# Lab9.net
KiCad netlist of a schematic drawn in EAGLE
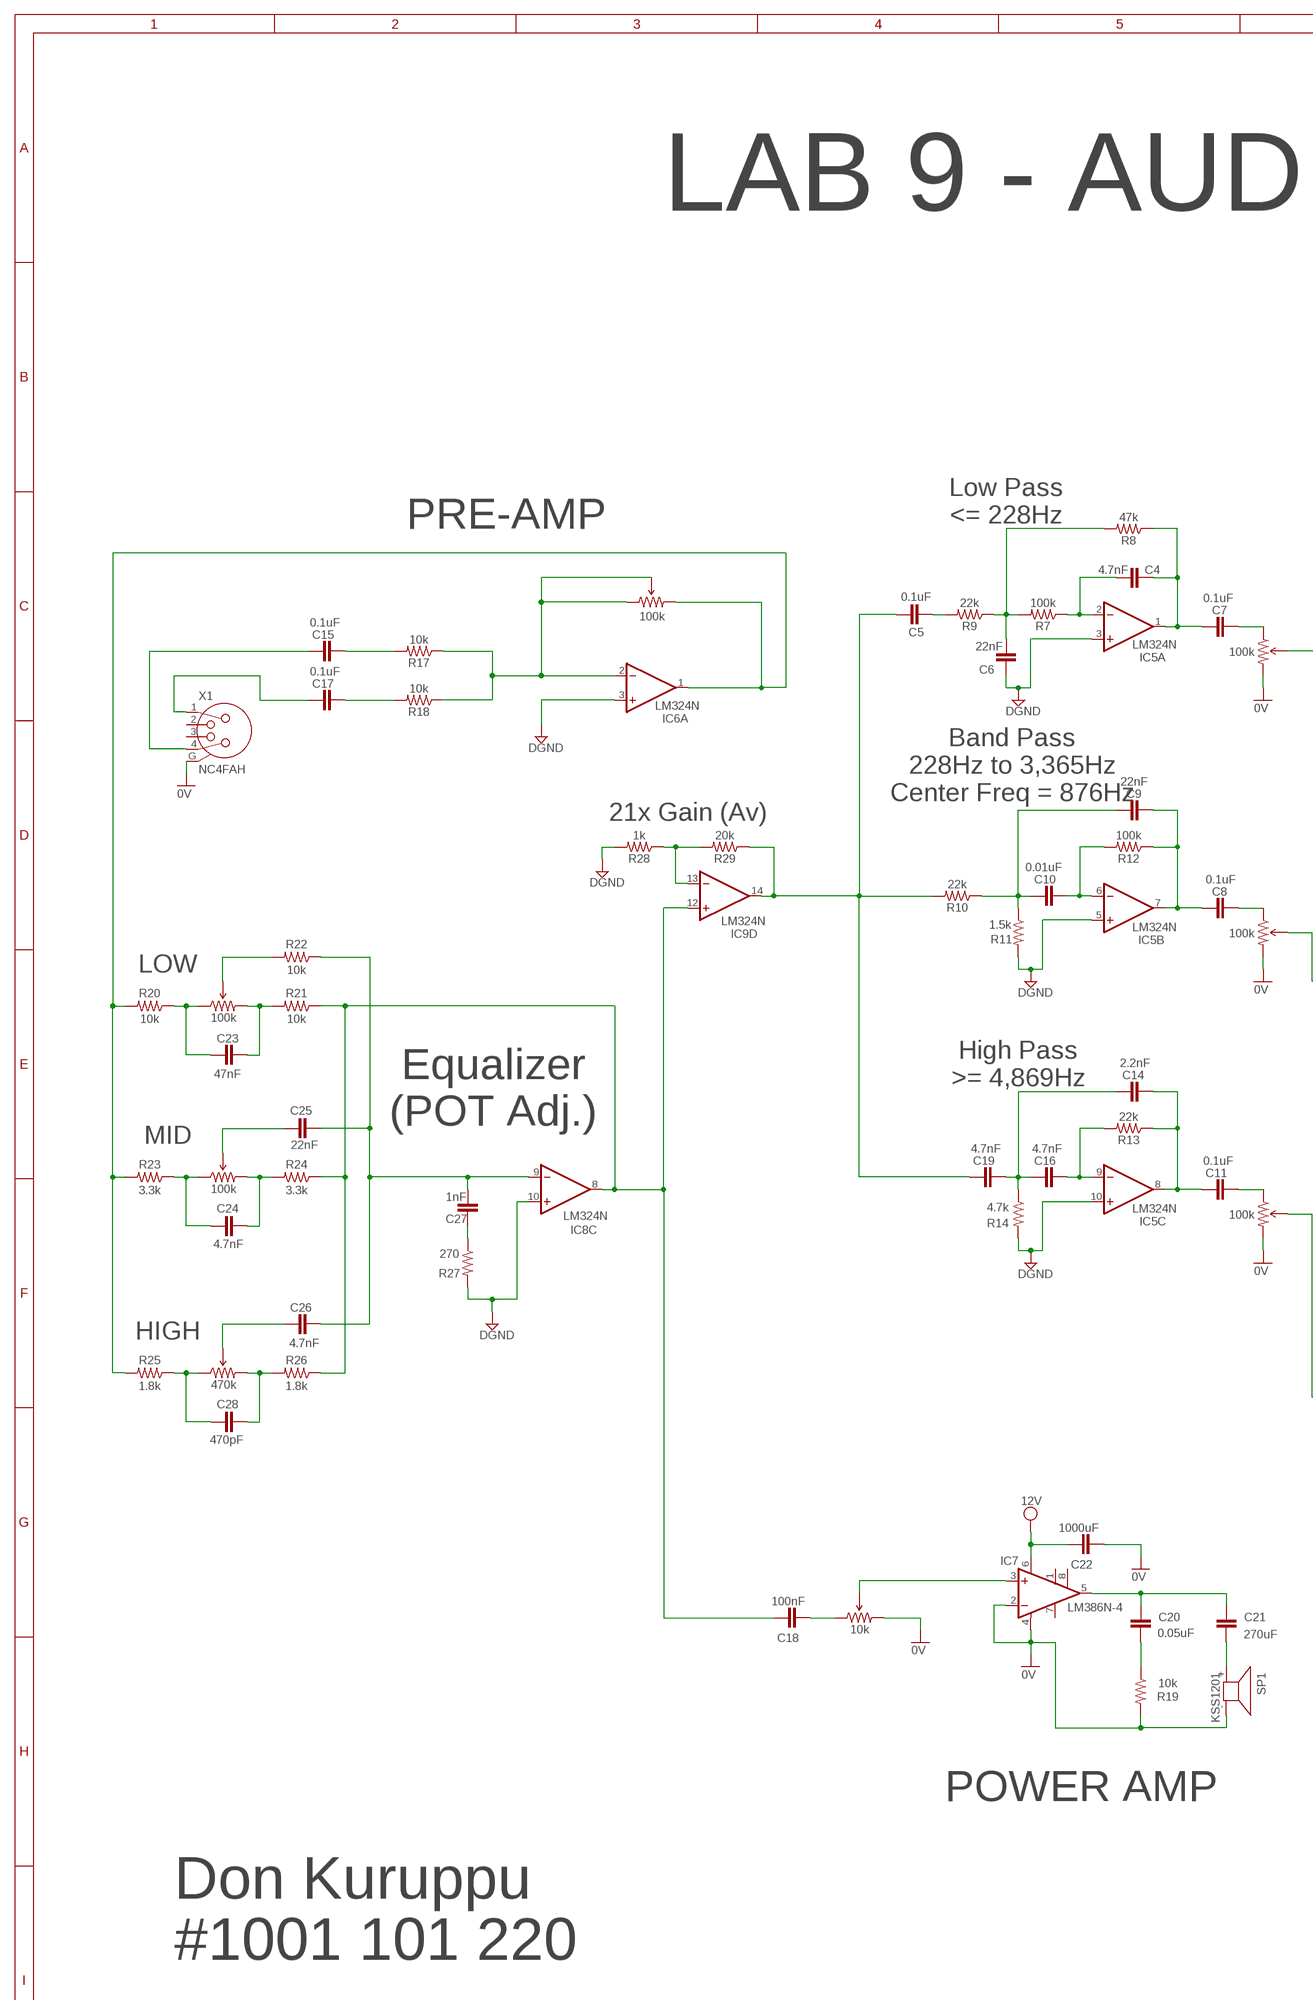
[diagram p0: schematic, sheet 1, part 1 of 2]
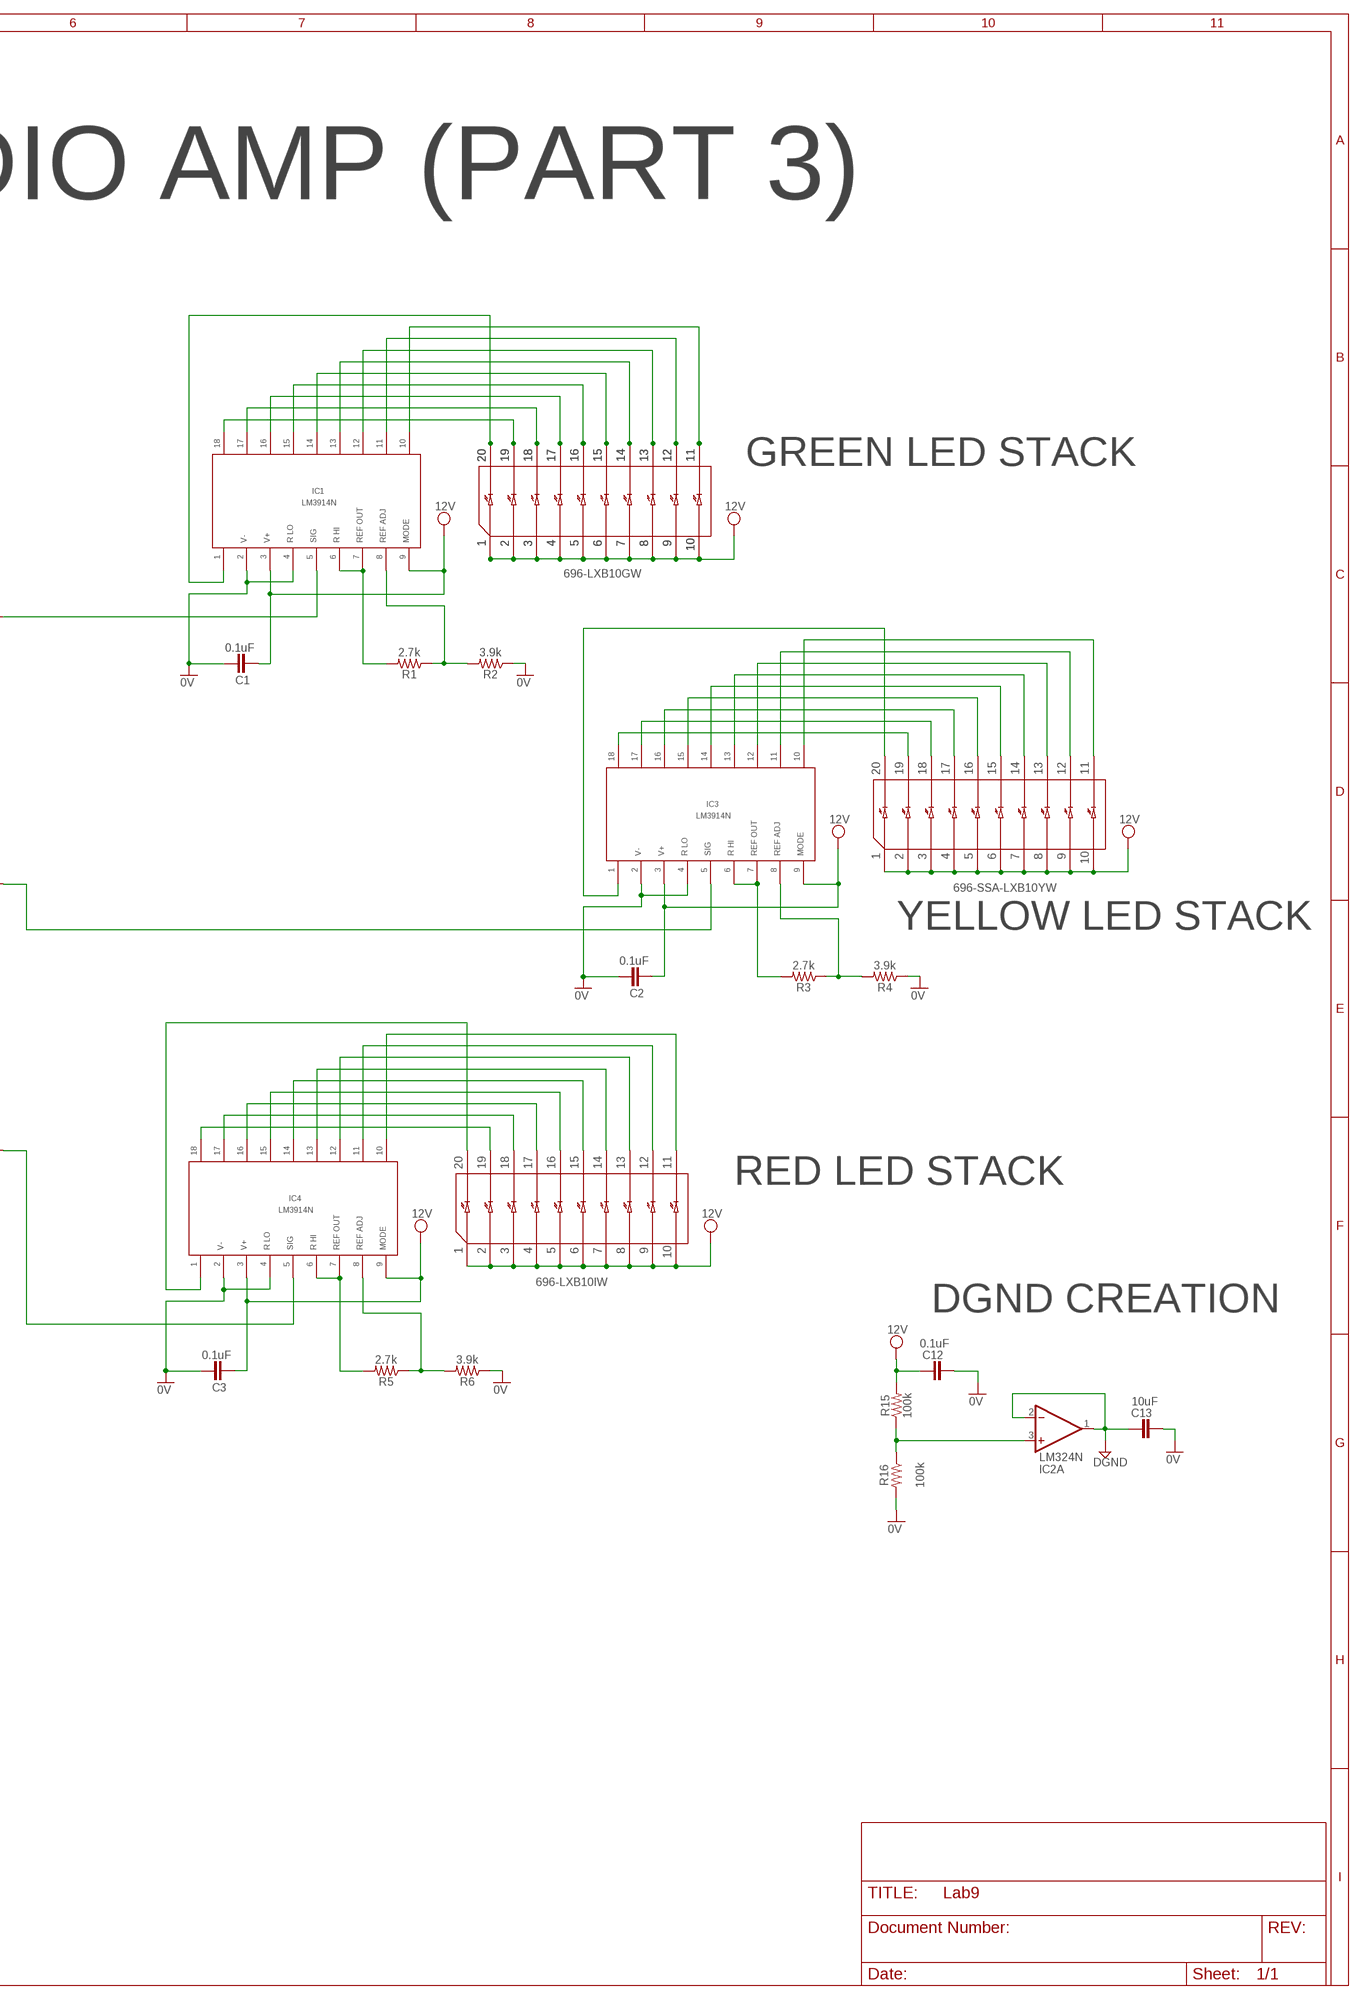
[diagram p1: schematic, sheet 1, part 2 of 2]

(export (version "E")
  (design (tool "Eeschema 10.0.6"))
  (components
    (comp (ref "C1")
      (value "0.1uF")
      (footprint "eagle-import:CAP-PTH-SMALL-KIT")
      (libsource (lib "eagle-import") (part "0.1UF-KIT-EZ-50V-20%"))
    )
    (comp (ref "C2")
      (value "0.1uF")
      (footprint "eagle-import:CAP-PTH-SMALL-KIT")
      (libsource (lib "eagle-import") (part "0.1UF-KIT-EZ-50V-20%"))
    )
    (comp (ref "C3")
      (value "0.1uF")
      (footprint "eagle-import:CAP-PTH-SMALL-KIT")
      (libsource (lib "eagle-import") (part "0.1UF-KIT-EZ-50V-20%"))
    )
    (comp (ref "C4")
      (value "4.7nF")
      (footprint "eagle-import:CAP-PTH-SMALL-KIT")
      (libsource (lib "eagle-import") (part "0.1UF-KIT-EZ-50V-20%"))
    )
    (comp (ref "C5")
      (value "0.1uF")
      (footprint "eagle-import:CAP-PTH-SMALL-KIT")
      (libsource (lib "eagle-import") (part "0.1UF-KIT-EZ-50V-20%"))
    )
    (comp (ref "C6")
      (value "22nF")
      (footprint "eagle-import:CAP-PTH-SMALL-KIT")
      (libsource (lib "eagle-import") (part "0.1UF-KIT-EZ-50V-20%"))
    )
    (comp (ref "C7")
      (value "0.1uF")
      (footprint "eagle-import:CAP-PTH-SMALL-KIT")
      (libsource (lib "eagle-import") (part "0.1UF-KIT-EZ-50V-20%"))
    )
    (comp (ref "C8")
      (value "0.1uF")
      (footprint "eagle-import:CAP-PTH-SMALL-KIT")
      (libsource (lib "eagle-import") (part "0.1UF-KIT-EZ-50V-20%"))
    )
    (comp (ref "C9")
      (value "22nF")
      (footprint "eagle-import:CAP-PTH-SMALL-KIT")
      (libsource (lib "eagle-import") (part "0.1UF-KIT-EZ-50V-20%"))
    )
    (comp (ref "C10")
      (value "0.01uF")
      (footprint "eagle-import:CAP-PTH-SMALL-KIT")
      (libsource (lib "eagle-import") (part "0.1UF-KIT-EZ-50V-20%"))
    )
    (comp (ref "C11")
      (value "0.1uF")
      (footprint "eagle-import:CAP-PTH-SMALL-KIT")
      (libsource (lib "eagle-import") (part "0.1UF-KIT-EZ-50V-20%"))
    )
    (comp (ref "C12")
      (value "0.1uF")
      (footprint "eagle-import:CAP-PTH-SMALL-KIT")
      (libsource (lib "eagle-import") (part "0.1UF-KIT-EZ-50V-20%"))
    )
    (comp (ref "C13")
      (value "10uF")
      (footprint "eagle-import:CAP-PTH-SMALL-KIT")
      (libsource (lib "eagle-import") (part "0.1UF-KIT-EZ-50V-20%"))
    )
    (comp (ref "C14")
      (value "2.2nF")
      (footprint "eagle-import:CAP-PTH-SMALL-KIT")
      (libsource (lib "eagle-import") (part "0.1UF-KIT-EZ-50V-20%"))
    )
    (comp (ref "C15")
      (value "0.1uF")
      (footprint "eagle-import:CAP-PTH-SMALL-KIT")
      (libsource (lib "eagle-import") (part "0.1UF-KIT-EZ-50V-20%"))
    )
    (comp (ref "C16")
      (value "4.7nF")
      (footprint "eagle-import:CAP-PTH-SMALL-KIT")
      (libsource (lib "eagle-import") (part "0.1UF-KIT-EZ-50V-20%"))
    )
    (comp (ref "C17")
      (value "0.1uF")
      (footprint "eagle-import:CAP-PTH-SMALL-KIT")
      (libsource (lib "eagle-import") (part "0.1UF-KIT-EZ-50V-20%"))
    )
    (comp (ref "C18")
      (value "100nF")
      (footprint "eagle-import:CAP-PTH-SMALL-KIT")
      (libsource (lib "eagle-import") (part "0.1UF-KIT-EZ-50V-20%"))
    )
    (comp (ref "C19")
      (value "4.7nF")
      (footprint "eagle-import:CAP-PTH-SMALL-KIT")
      (libsource (lib "eagle-import") (part "0.1UF-KIT-EZ-50V-20%"))
    )
    (comp (ref "C20")
      (value "0.05uF")
      (footprint "eagle-import:CAP-PTH-SMALL-KIT")
      (libsource (lib "eagle-import") (part "0.1UF-KIT-EZ-50V-20%"))
    )
    (comp (ref "C21")
      (value "270uF")
      (footprint "eagle-import:CAP-PTH-SMALL-KIT")
      (libsource (lib "eagle-import") (part "0.1UF-KIT-EZ-50V-20%"))
    )
    (comp (ref "C22")
      (value "1000uF")
      (footprint "eagle-import:CAP-PTH-SMALL-KIT")
      (libsource (lib "eagle-import") (part "0.1UF-KIT-EZ-50V-20%"))
    )
    (comp (ref "C23")
      (value "47nF")
      (footprint "eagle-import:CAP-PTH-SMALL-KIT")
      (libsource (lib "eagle-import") (part "0.1UF-KIT-EZ-50V-20%"))
    )
    (comp (ref "C24")
      (value "4.7nF")
      (footprint "eagle-import:CAP-PTH-SMALL-KIT")
      (libsource (lib "eagle-import") (part "0.1UF-KIT-EZ-50V-20%"))
    )
    (comp (ref "C25")
      (value "22nF")
      (footprint "eagle-import:CAP-PTH-SMALL-KIT")
      (libsource (lib "eagle-import") (part "0.1UF-KIT-EZ-50V-20%"))
    )
    (comp (ref "C26")
      (value "4.7nF")
      (footprint "eagle-import:CAP-PTH-SMALL-KIT")
      (libsource (lib "eagle-import") (part "0.1UF-KIT-EZ-50V-20%"))
    )
    (comp (ref "C27")
      (value "1nF")
      (footprint "eagle-import:CAP-PTH-SMALL-KIT")
      (libsource (lib "eagle-import") (part "0.1UF-KIT-EZ-50V-20%"))
    )
    (comp (ref "C28")
      (value "470pF")
      (footprint "eagle-import:CAP-PTH-SMALL-KIT")
      (libsource (lib "eagle-import") (part "0.1UF-KIT-EZ-50V-20%"))
    )
    (comp (ref "IC1")
      (value "LM3914N")
      (footprint "eagle-import:DIL18")
      (libsource (lib "eagle-import") (part "LM3914N"))
    )
    (comp (ref "IC2")
      (value "LM324N")
      (footprint "eagle-import:DIL14")
      (libsource (lib "eagle-import") (part "LM324N"))
    )
    (comp (ref "IC3")
      (value "LM3914N")
      (footprint "eagle-import:DIL18")
      (libsource (lib "eagle-import") (part "LM3914N"))
    )
    (comp (ref "IC4")
      (value "LM3914N")
      (footprint "eagle-import:DIL18")
      (libsource (lib "eagle-import") (part "LM3914N"))
    )
    (comp (ref "IC5")
      (value "LM324N")
      (footprint "eagle-import:DIL14")
      (libsource (lib "eagle-import") (part "LM324N"))
    )
    (comp (ref "IC6")
      (value "LM324N")
      (footprint "eagle-import:DIL14")
      (libsource (lib "eagle-import") (part "LM324N"))
    )
    (comp (ref "IC7")
      (value "LM386N-4")
      (footprint "eagle-import:DIL08")
      (libsource (lib "eagle-import") (part "LM386?-N4"))
    )
    (comp (ref "IC8")
      (value "LM324N")
      (footprint "eagle-import:DIL14")
      (libsource (lib "eagle-import") (part "LM324N"))
    )
    (comp (ref "IC9")
      (value "LM324N")
      (footprint "eagle-import:DIL14")
      (libsource (lib "eagle-import") (part "LM324N"))
    )
    (comp (ref "POT1")
      (value "100k")
      (footprint "eagle-import:TRIM_POT_PTH")
      (libsource (lib "eagle-import") (part "TRIMPOT"))
    )
    (comp (ref "POT2")
      (value "100k")
      (footprint "eagle-import:TRIM_POT_PTH")
      (libsource (lib "eagle-import") (part "TRIMPOT"))
    )
    (comp (ref "POT3")
      (value "100k")
      (footprint "eagle-import:TRIM_POT_PTH")
      (libsource (lib "eagle-import") (part "TRIMPOT"))
    )
    (comp (ref "POT4")
      (value "100k")
      (footprint "eagle-import:TRIM_POT_PTH")
      (libsource (lib "eagle-import") (part "TRIMPOT"))
    )
    (comp (ref "POT5")
      (value "10k")
      (footprint "eagle-import:TRIM_POT_PTH")
      (libsource (lib "eagle-import") (part "TRIMPOT"))
    )
    (comp (ref "POT6")
      (value "100k")
      (footprint "eagle-import:TRIM_POT_PTH")
      (libsource (lib "eagle-import") (part "TRIMPOT"))
    )
    (comp (ref "POT7")
      (value "100k")
      (footprint "eagle-import:TRIM_POT_PTH")
      (libsource (lib "eagle-import") (part "TRIMPOT"))
    )
    (comp (ref "POT8")
      (value "470k")
      (footprint "eagle-import:TRIM_POT_PTH")
      (libsource (lib "eagle-import") (part "TRIMPOT"))
    )
    (comp (ref "R1")
      (value "2.7k")
      (footprint "eagle-import:AXIAL-0.3")
      (libsource (lib "eagle-import") (part "100KOHM-HORIZ-1/4W-1%"))
    )
    (comp (ref "R2")
      (value "3.9k")
      (footprint "eagle-import:AXIAL-0.3")
      (libsource (lib "eagle-import") (part "100KOHM-HORIZ-1/4W-1%"))
    )
    (comp (ref "R3")
      (value "2.7k")
      (footprint "eagle-import:AXIAL-0.3")
      (libsource (lib "eagle-import") (part "100KOHM-HORIZ-1/4W-1%"))
    )
    (comp (ref "R4")
      (value "3.9k")
      (footprint "eagle-import:AXIAL-0.3")
      (libsource (lib "eagle-import") (part "100KOHM-HORIZ-1/4W-1%"))
    )
    (comp (ref "R5")
      (value "2.7k")
      (footprint "eagle-import:AXIAL-0.3")
      (libsource (lib "eagle-import") (part "100KOHM-HORIZ-1/4W-1%"))
    )
    (comp (ref "R6")
      (value "3.9k")
      (footprint "eagle-import:AXIAL-0.3")
      (libsource (lib "eagle-import") (part "100KOHM-HORIZ-1/4W-1%"))
    )
    (comp (ref "R7")
      (value "100k")
      (footprint "eagle-import:AXIAL-0.3")
      (libsource (lib "eagle-import") (part "100KOHM-HORIZ-1/4W-1%"))
    )
    (comp (ref "R8")
      (value "47k")
      (footprint "eagle-import:AXIAL-0.3")
      (libsource (lib "eagle-import") (part "100KOHM-HORIZ-1/4W-1%"))
    )
    (comp (ref "R9")
      (value "22k")
      (footprint "eagle-import:AXIAL-0.3")
      (libsource (lib "eagle-import") (part "100KOHM-HORIZ-1/4W-1%"))
    )
    (comp (ref "R10")
      (value "22k")
      (footprint "eagle-import:AXIAL-0.3")
      (libsource (lib "eagle-import") (part "100KOHM-HORIZ-1/4W-1%"))
    )
    (comp (ref "R11")
      (value "1.5k")
      (footprint "eagle-import:AXIAL-0.3")
      (libsource (lib "eagle-import") (part "100KOHM-HORIZ-1/4W-1%"))
    )
    (comp (ref "R12")
      (value "100k")
      (footprint "eagle-import:AXIAL-0.3")
      (libsource (lib "eagle-import") (part "100KOHM-HORIZ-1/4W-1%"))
    )
    (comp (ref "R13")
      (value "22k")
      (footprint "eagle-import:AXIAL-0.3")
      (libsource (lib "eagle-import") (part "100KOHM-HORIZ-1/4W-1%"))
    )
    (comp (ref "R14")
      (value "4.7k")
      (footprint "eagle-import:AXIAL-0.3")
      (libsource (lib "eagle-import") (part "100KOHM-HORIZ-1/4W-1%"))
    )
    (comp (ref "R15")
      (value "100k")
      (footprint "eagle-import:AXIAL-0.3")
      (libsource (lib "eagle-import") (part "100KOHM-HORIZ-1/4W-1%"))
    )
    (comp (ref "R16")
      (value "100k")
      (footprint "eagle-import:AXIAL-0.3")
      (libsource (lib "eagle-import") (part "100KOHM-HORIZ-1/4W-1%"))
    )
    (comp (ref "R17")
      (value "10k")
      (footprint "eagle-import:AXIAL-0.3")
      (libsource (lib "eagle-import") (part "100KOHM-HORIZ-1/4W-1%"))
    )
    (comp (ref "R18")
      (value "10k")
      (footprint "eagle-import:AXIAL-0.3")
      (libsource (lib "eagle-import") (part "100KOHM-HORIZ-1/4W-1%"))
    )
    (comp (ref "R19")
      (value "10k")
      (footprint "eagle-import:AXIAL-0.3")
      (libsource (lib "eagle-import") (part "100KOHM-HORIZ-1/4W-1%"))
    )
    (comp (ref "R20")
      (value "10k")
      (footprint "eagle-import:AXIAL-0.3")
      (libsource (lib "eagle-import") (part "100KOHM-HORIZ-1/4W-1%"))
    )
    (comp (ref "R21")
      (value "10k")
      (footprint "eagle-import:AXIAL-0.3")
      (libsource (lib "eagle-import") (part "100KOHM-HORIZ-1/4W-1%"))
    )
    (comp (ref "R22")
      (value "10k")
      (footprint "eagle-import:AXIAL-0.3")
      (libsource (lib "eagle-import") (part "100KOHM-HORIZ-1/4W-1%"))
    )
    (comp (ref "R23")
      (value "3.3k")
      (footprint "eagle-import:AXIAL-0.3")
      (libsource (lib "eagle-import") (part "100KOHM-HORIZ-1/4W-1%"))
    )
    (comp (ref "R24")
      (value "3.3k")
      (footprint "eagle-import:AXIAL-0.3")
      (libsource (lib "eagle-import") (part "100KOHM-HORIZ-1/4W-1%"))
    )
    (comp (ref "R25")
      (value "1.8k")
      (footprint "eagle-import:AXIAL-0.3")
      (libsource (lib "eagle-import") (part "100KOHM-HORIZ-1/4W-1%"))
    )
    (comp (ref "R26")
      (value "1.8k")
      (footprint "eagle-import:AXIAL-0.3")
      (libsource (lib "eagle-import") (part "100KOHM-HORIZ-1/4W-1%"))
    )
    (comp (ref "R27")
      (value "270")
      (footprint "eagle-import:AXIAL-0.3")
      (libsource (lib "eagle-import") (part "100KOHM-HORIZ-1/4W-1%"))
    )
    (comp (ref "R28")
      (value "1k")
      (footprint "eagle-import:AXIAL-0.3")
      (libsource (lib "eagle-import") (part "100KOHM-HORIZ-1/4W-1%"))
    )
    (comp (ref "R29")
      (value "20k")
      (footprint "eagle-import:AXIAL-0.3")
      (libsource (lib "eagle-import") (part "100KOHM-HORIZ-1/4W-1%"))
    )
    (comp (ref "SP1")
      (value "KSS1201")
      (footprint "eagle-import:KSS1201")
      (libsource (lib "eagle-import") (part "KSS1201"))
    )
    (comp (ref "STACK1")
      (value "696-LXB10GW")
      (footprint "eagle-import:LED_STACK_PROTO")
      (libsource (lib "eagle-import") (part "696-LXB10GW"))
    )
    (comp (ref "STACK2")
      (value "696-LXB10GW")
      (footprint "eagle-import:LED_STACK_PROTO")
      (libsource (lib "eagle-import") (part "696-LXB10GW"))
    )
    (comp (ref "STACK3")
      (value "696-SSA-LXB10YW")
      (footprint "eagle-import:LED_STACK_PROTO")
      (libsource (lib "eagle-import") (part "696-SSA-LXB10YW"))
    )
    (comp (ref "STACK4")
      (value "696-LXB10IW")
      (footprint "eagle-import:LED_STACK_PROTO")
      (libsource (lib "eagle-import") (part "696-LXB10IW"))
    )
    (comp (ref "X1")
      (value "NC4FAH")
      (footprint "eagle-import:NC4FAH")
      (libsource (lib "eagle-import") (part "NC4FAH"))
    )
  )
  (nets
    (net (code "1") (name "0V") (class "Default")
      (node (ref "C1") (pin "1") (pinfunction "1_1") (pintype "passive"))
      (node (ref "C12") (pin "2") (pinfunction "2_2") (pintype "passive"))
      (node (ref "C13") (pin "2") (pinfunction "2_2") (pintype "passive"))
      (node (ref "C2") (pin "1") (pinfunction "1_1") (pintype "passive"))
      (node (ref "C22") (pin "2") (pinfunction "2_2") (pintype "passive"))
      (node (ref "C3") (pin "1") (pinfunction "1_1") (pintype "passive"))
      (node (ref "IC1") (pin "2") (pinfunction "P$2_2") (pintype "bidirectional"))
      (node (ref "IC1") (pin "4") (pinfunction "P$4_4") (pintype "bidirectional"))
      (node (ref "IC3") (pin "2") (pinfunction "P$2_2") (pintype "bidirectional"))
      (node (ref "IC3") (pin "4") (pinfunction "P$4_4") (pintype "bidirectional"))
      (node (ref "IC4") (pin "2") (pinfunction "P$2_2") (pintype "bidirectional"))
      (node (ref "IC4") (pin "4") (pinfunction "P$4_4") (pintype "bidirectional"))
      (node (ref "IC7") (pin "2") (pinfunction "-IN_2") (pintype "input"))
      (node (ref "IC7") (pin "4") (pinfunction "GND_4") (pintype "power_in"))
      (node (ref "POT1") (pin "3") (pinfunction "CW_3") (pintype "passive"))
      (node (ref "POT2") (pin "3") (pinfunction "CW_3") (pintype "passive"))
      (node (ref "POT3") (pin "3") (pinfunction "CW_3") (pintype "passive"))
      (node (ref "POT5") (pin "3") (pinfunction "CW_3") (pintype "passive"))
      (node (ref "R16") (pin "P$2") (pinfunction "2_P$2") (pintype "passive"))
      (node (ref "R19") (pin "P$2") (pinfunction "2_P$2") (pintype "passive"))
      (node (ref "R2") (pin "P$1") (pinfunction "1_P$1") (pintype "passive"))
      (node (ref "R4") (pin "P$1") (pinfunction "1_P$1") (pintype "passive"))
      (node (ref "R6") (pin "P$1") (pinfunction "1_P$1") (pintype "passive"))
      (node (ref "SP1") (pin "-") (pinfunction "2_-") (pintype "passive"))
      (node (ref "X1") (pin "G") (pinfunction "G_G") (pintype "passive"))
    )
    (net (code "2") (name "DGND") (class "Default")
      (node (ref "C13") (pin "1") (pinfunction "1_1") (pintype "passive"))
      (node (ref "C6") (pin "1") (pinfunction "1_1") (pintype "passive"))
      (node (ref "IC2") (pin "1") (pinfunction "OUT_1") (pintype "output"))
      (node (ref "IC2") (pin "2") (pinfunction "-IN_2") (pintype "input"))
      (node (ref "IC5") (pin "10") (pinfunction "+IN_10") (pintype "input"))
      (node (ref "IC5") (pin "3") (pinfunction "+IN_3") (pintype "input"))
      (node (ref "IC5") (pin "5") (pinfunction "+IN_5") (pintype "input"))
      (node (ref "IC6") (pin "3") (pinfunction "+IN_3") (pintype "input"))
      (node (ref "IC8") (pin "10") (pinfunction "+IN_10") (pintype "input"))
      (node (ref "R11") (pin "P$2") (pinfunction "2_P$2") (pintype "passive"))
      (node (ref "R14") (pin "P$2") (pinfunction "2_P$2") (pintype "passive"))
      (node (ref "R27") (pin "P$2") (pinfunction "2_P$2") (pintype "passive"))
      (node (ref "R28") (pin "P$2") (pinfunction "2_P$2") (pintype "passive"))
    )
    (net (code "3") (name "Net-(C15-Pad1)") (class "Default")
      (node (ref "C15") (pin "1") (pinfunction "1_1") (pintype "passive"))
      (node (ref "X1") (pin "4") (pinfunction "4_4") (pintype "passive"))
    )
    (net (code "4") (name "Net-(C17-Pad1)") (class "Default")
      (node (ref "C17") (pin "1") (pinfunction "1_1") (pintype "passive"))
      (node (ref "X1") (pin "1") (pinfunction "1_1") (pintype "passive"))
    )
    (net (code "5") (name "Net-(IC1-P$1)") (class "Default")
      (node (ref "IC1") (pin "1") (pinfunction "P$1_1") (pintype "bidirectional"))
      (node (ref "STACK1") (pin "P$11") (pinfunction "P$11_P$11") (pintype "bidirectional"))
      (node (ref "STACK2") (pin "P$11") (pinfunction "P$11_P$11") (pintype "bidirectional"))
    )
    (net (code "6") (name "Net-(IC1-P$5)") (class "Default")
      (node (ref "IC1") (pin "5") (pinfunction "P$5_5") (pintype "bidirectional"))
      (node (ref "POT1") (pin "2") (pinfunction "WIPER_2") (pintype "passive"))
    )
    (net (code "7") (name "Net-(IC1-P$6)") (class "Default")
      (node (ref "IC1") (pin "6") (pinfunction "P$6_6") (pintype "bidirectional"))
      (node (ref "IC1") (pin "7") (pinfunction "P$7_7") (pintype "bidirectional"))
      (node (ref "R1") (pin "P$2") (pinfunction "2_P$2") (pintype "passive"))
    )
    (net (code "8") (name "Net-(IC1-P$8)") (class "Default")
      (node (ref "IC1") (pin "8") (pinfunction "P$8_8") (pintype "bidirectional"))
      (node (ref "R1") (pin "P$1") (pinfunction "1_P$1") (pintype "passive"))
      (node (ref "R2") (pin "P$2") (pinfunction "2_P$2") (pintype "passive"))
    )
    (net (code "9") (name "Net-(IC1-P$10)") (class "Default")
      (node (ref "IC1") (pin "10") (pinfunction "P$10_10") (pintype "bidirectional"))
      (node (ref "STACK1") (pin "P$20") (pinfunction "P$20_P$20") (pintype "bidirectional"))
      (node (ref "STACK2") (pin "P$20") (pinfunction "P$20_P$20") (pintype "bidirectional"))
    )
    (net (code "10") (name "Net-(IC1-P$11)") (class "Default")
      (node (ref "IC1") (pin "11") (pinfunction "P$11_11") (pintype "bidirectional"))
      (node (ref "STACK1") (pin "P$19") (pinfunction "P$19_P$19") (pintype "bidirectional"))
      (node (ref "STACK2") (pin "P$19") (pinfunction "P$19_P$19") (pintype "bidirectional"))
    )
    (net (code "11") (name "Net-(IC1-P$12)") (class "Default")
      (node (ref "IC1") (pin "12") (pinfunction "P$12_12") (pintype "bidirectional"))
      (node (ref "STACK1") (pin "P$18") (pinfunction "P$18_P$18") (pintype "bidirectional"))
      (node (ref "STACK2") (pin "P$18") (pinfunction "P$18_P$18") (pintype "bidirectional"))
    )
    (net (code "12") (name "Net-(IC1-P$13)") (class "Default")
      (node (ref "IC1") (pin "13") (pinfunction "P$13_13") (pintype "bidirectional"))
      (node (ref "STACK1") (pin "P$17") (pinfunction "P$17_P$17") (pintype "bidirectional"))
      (node (ref "STACK2") (pin "P$17") (pinfunction "P$17_P$17") (pintype "bidirectional"))
    )
    (net (code "13") (name "Net-(IC1-P$14)") (class "Default")
      (node (ref "IC1") (pin "14") (pinfunction "P$14_14") (pintype "bidirectional"))
      (node (ref "STACK1") (pin "P$16") (pinfunction "P$16_P$16") (pintype "bidirectional"))
      (node (ref "STACK2") (pin "P$16") (pinfunction "P$16_P$16") (pintype "bidirectional"))
    )
    (net (code "14") (name "Net-(IC1-P$15)") (class "Default")
      (node (ref "IC1") (pin "15") (pinfunction "P$15_15") (pintype "bidirectional"))
      (node (ref "STACK1") (pin "P$15") (pinfunction "P$15_P$15") (pintype "bidirectional"))
      (node (ref "STACK2") (pin "P$15") (pinfunction "P$15_P$15") (pintype "bidirectional"))
    )
    (net (code "15") (name "Net-(IC1-P$16)") (class "Default")
      (node (ref "IC1") (pin "16") (pinfunction "P$16_16") (pintype "bidirectional"))
      (node (ref "STACK1") (pin "P$14") (pinfunction "P$14_P$14") (pintype "bidirectional"))
      (node (ref "STACK2") (pin "P$14") (pinfunction "P$14_P$14") (pintype "bidirectional"))
    )
    (net (code "16") (name "Net-(IC1-P$17)") (class "Default")
      (node (ref "IC1") (pin "17") (pinfunction "P$17_17") (pintype "bidirectional"))
      (node (ref "STACK1") (pin "P$13") (pinfunction "P$13_P$13") (pintype "bidirectional"))
      (node (ref "STACK2") (pin "P$13") (pinfunction "P$13_P$13") (pintype "bidirectional"))
    )
    (net (code "17") (name "Net-(IC1-P$18)") (class "Default")
      (node (ref "IC1") (pin "18") (pinfunction "P$18_18") (pintype "bidirectional"))
      (node (ref "STACK1") (pin "P$12") (pinfunction "P$12_P$12") (pintype "bidirectional"))
      (node (ref "STACK2") (pin "P$12") (pinfunction "P$12_P$12") (pintype "bidirectional"))
    )
    (net (code "18") (name "Net-(IC2A-+IN)") (class "Default")
      (node (ref "IC2") (pin "3") (pinfunction "+IN_3") (pintype "input"))
      (node (ref "R15") (pin "P$1") (pinfunction "1_P$1") (pintype "passive"))
      (node (ref "R16") (pin "P$1") (pinfunction "1_P$1") (pintype "passive"))
    )
    (net (code "19") (name "Net-(IC3-P$1)") (class "Default")
      (node (ref "IC3") (pin "1") (pinfunction "P$1_1") (pintype "bidirectional"))
      (node (ref "STACK3") (pin "P$11") (pinfunction "P$11_P$11") (pintype "bidirectional"))
    )
    (net (code "20") (name "Net-(IC3-P$5)") (class "Default")
      (node (ref "IC3") (pin "5") (pinfunction "P$5_5") (pintype "bidirectional"))
      (node (ref "POT2") (pin "2") (pinfunction "WIPER_2") (pintype "passive"))
    )
    (net (code "21") (name "Net-(IC3-P$6)") (class "Default")
      (node (ref "IC3") (pin "6") (pinfunction "P$6_6") (pintype "bidirectional"))
      (node (ref "IC3") (pin "7") (pinfunction "P$7_7") (pintype "bidirectional"))
      (node (ref "R3") (pin "P$2") (pinfunction "2_P$2") (pintype "passive"))
    )
    (net (code "22") (name "Net-(IC3-P$8)") (class "Default")
      (node (ref "IC3") (pin "8") (pinfunction "P$8_8") (pintype "bidirectional"))
      (node (ref "R3") (pin "P$1") (pinfunction "1_P$1") (pintype "passive"))
      (node (ref "R4") (pin "P$2") (pinfunction "2_P$2") (pintype "passive"))
    )
    (net (code "23") (name "Net-(IC3-P$10)") (class "Default")
      (node (ref "IC3") (pin "10") (pinfunction "P$10_10") (pintype "bidirectional"))
      (node (ref "STACK3") (pin "P$20") (pinfunction "P$20_P$20") (pintype "bidirectional"))
    )
    (net (code "24") (name "Net-(IC3-P$11)") (class "Default")
      (node (ref "IC3") (pin "11") (pinfunction "P$11_11") (pintype "bidirectional"))
      (node (ref "STACK3") (pin "P$19") (pinfunction "P$19_P$19") (pintype "bidirectional"))
    )
    (net (code "25") (name "Net-(IC3-P$12)") (class "Default")
      (node (ref "IC3") (pin "12") (pinfunction "P$12_12") (pintype "bidirectional"))
      (node (ref "STACK3") (pin "P$18") (pinfunction "P$18_P$18") (pintype "bidirectional"))
    )
    (net (code "26") (name "Net-(IC3-P$13)") (class "Default")
      (node (ref "IC3") (pin "13") (pinfunction "P$13_13") (pintype "bidirectional"))
      (node (ref "STACK3") (pin "P$17") (pinfunction "P$17_P$17") (pintype "bidirectional"))
    )
    (net (code "27") (name "Net-(IC3-P$14)") (class "Default")
      (node (ref "IC3") (pin "14") (pinfunction "P$14_14") (pintype "bidirectional"))
      (node (ref "STACK3") (pin "P$16") (pinfunction "P$16_P$16") (pintype "bidirectional"))
    )
    (net (code "28") (name "Net-(IC3-P$15)") (class "Default")
      (node (ref "IC3") (pin "15") (pinfunction "P$15_15") (pintype "bidirectional"))
      (node (ref "STACK3") (pin "P$15") (pinfunction "P$15_P$15") (pintype "bidirectional"))
    )
    (net (code "29") (name "Net-(IC3-P$16)") (class "Default")
      (node (ref "IC3") (pin "16") (pinfunction "P$16_16") (pintype "bidirectional"))
      (node (ref "STACK3") (pin "P$14") (pinfunction "P$14_P$14") (pintype "bidirectional"))
    )
    (net (code "30") (name "Net-(IC3-P$17)") (class "Default")
      (node (ref "IC3") (pin "17") (pinfunction "P$17_17") (pintype "bidirectional"))
      (node (ref "STACK3") (pin "P$13") (pinfunction "P$13_P$13") (pintype "bidirectional"))
    )
    (net (code "31") (name "Net-(IC3-P$18)") (class "Default")
      (node (ref "IC3") (pin "18") (pinfunction "P$18_18") (pintype "bidirectional"))
      (node (ref "STACK3") (pin "P$12") (pinfunction "P$12_P$12") (pintype "bidirectional"))
    )
    (net (code "32") (name "Net-(IC4-P$1)") (class "Default")
      (node (ref "IC4") (pin "1") (pinfunction "P$1_1") (pintype "bidirectional"))
      (node (ref "STACK4") (pin "P$11") (pinfunction "P$11_P$11") (pintype "bidirectional"))
    )
    (net (code "33") (name "Net-(IC4-P$5)") (class "Default")
      (node (ref "IC4") (pin "5") (pinfunction "P$5_5") (pintype "bidirectional"))
      (node (ref "POT3") (pin "2") (pinfunction "WIPER_2") (pintype "passive"))
    )
    (net (code "34") (name "Net-(IC4-P$6)") (class "Default")
      (node (ref "IC4") (pin "6") (pinfunction "P$6_6") (pintype "bidirectional"))
      (node (ref "IC4") (pin "7") (pinfunction "P$7_7") (pintype "bidirectional"))
      (node (ref "R5") (pin "P$2") (pinfunction "2_P$2") (pintype "passive"))
    )
    (net (code "35") (name "Net-(IC4-P$8)") (class "Default")
      (node (ref "IC4") (pin "8") (pinfunction "P$8_8") (pintype "bidirectional"))
      (node (ref "R5") (pin "P$1") (pinfunction "1_P$1") (pintype "passive"))
      (node (ref "R6") (pin "P$2") (pinfunction "2_P$2") (pintype "passive"))
    )
    (net (code "36") (name "Net-(IC4-P$10)") (class "Default")
      (node (ref "IC4") (pin "10") (pinfunction "P$10_10") (pintype "bidirectional"))
      (node (ref "STACK4") (pin "P$20") (pinfunction "P$20_P$20") (pintype "bidirectional"))
    )
    (net (code "37") (name "Net-(IC4-P$11)") (class "Default")
      (node (ref "IC4") (pin "11") (pinfunction "P$11_11") (pintype "bidirectional"))
      (node (ref "STACK4") (pin "P$19") (pinfunction "P$19_P$19") (pintype "bidirectional"))
    )
    (net (code "38") (name "Net-(IC4-P$12)") (class "Default")
      (node (ref "IC4") (pin "12") (pinfunction "P$12_12") (pintype "bidirectional"))
      (node (ref "STACK4") (pin "P$18") (pinfunction "P$18_P$18") (pintype "bidirectional"))
    )
    (net (code "39") (name "Net-(IC4-P$13)") (class "Default")
      (node (ref "IC4") (pin "13") (pinfunction "P$13_13") (pintype "bidirectional"))
      (node (ref "STACK4") (pin "P$17") (pinfunction "P$17_P$17") (pintype "bidirectional"))
    )
    (net (code "40") (name "Net-(IC4-P$14)") (class "Default")
      (node (ref "IC4") (pin "14") (pinfunction "P$14_14") (pintype "bidirectional"))
      (node (ref "STACK4") (pin "P$16") (pinfunction "P$16_P$16") (pintype "bidirectional"))
    )
    (net (code "41") (name "Net-(IC4-P$15)") (class "Default")
      (node (ref "IC4") (pin "15") (pinfunction "P$15_15") (pintype "bidirectional"))
      (node (ref "STACK4") (pin "P$15") (pinfunction "P$15_P$15") (pintype "bidirectional"))
    )
    (net (code "42") (name "Net-(IC4-P$16)") (class "Default")
      (node (ref "IC4") (pin "16") (pinfunction "P$16_16") (pintype "bidirectional"))
      (node (ref "STACK4") (pin "P$14") (pinfunction "P$14_P$14") (pintype "bidirectional"))
    )
    (net (code "43") (name "Net-(IC4-P$17)") (class "Default")
      (node (ref "IC4") (pin "17") (pinfunction "P$17_17") (pintype "bidirectional"))
      (node (ref "STACK4") (pin "P$13") (pinfunction "P$13_P$13") (pintype "bidirectional"))
    )
    (net (code "44") (name "Net-(IC4-P$18)") (class "Default")
      (node (ref "IC4") (pin "18") (pinfunction "P$18_18") (pintype "bidirectional"))
      (node (ref "STACK4") (pin "P$12") (pinfunction "P$12_P$12") (pintype "bidirectional"))
    )
    (net (code "45") (name "Net-(IC5A--IN)") (class "Default")
      (node (ref "C4") (pin "1") (pinfunction "1_1") (pintype "passive"))
      (node (ref "IC5") (pin "2") (pinfunction "-IN_2") (pintype "input"))
      (node (ref "R7") (pin "P$1") (pinfunction "1_P$1") (pintype "passive"))
    )
    (net (code "46") (name "Net-(IC5A-OUT)") (class "Default")
      (node (ref "C4") (pin "2") (pinfunction "2_2") (pintype "passive"))
      (node (ref "C7") (pin "1") (pinfunction "1_1") (pintype "passive"))
      (node (ref "IC5") (pin "1") (pinfunction "OUT_1") (pintype "output"))
      (node (ref "R8") (pin "P$1") (pinfunction "1_P$1") (pintype "passive"))
    )
    (net (code "47") (name "Net-(IC5B--IN)") (class "Default")
      (node (ref "C10") (pin "2") (pinfunction "2_2") (pintype "passive"))
      (node (ref "IC5") (pin "6") (pinfunction "-IN_6") (pintype "input"))
      (node (ref "R12") (pin "P$2") (pinfunction "2_P$2") (pintype "passive"))
    )
    (net (code "48") (name "Net-(IC5B-OUT)") (class "Default")
      (node (ref "C8") (pin "1") (pinfunction "1_1") (pintype "passive"))
      (node (ref "C9") (pin "2") (pinfunction "2_2") (pintype "passive"))
      (node (ref "IC5") (pin "7") (pinfunction "OUT_7") (pintype "output"))
      (node (ref "R12") (pin "P$1") (pinfunction "1_P$1") (pintype "passive"))
    )
    (net (code "49") (name "Net-(IC5C--IN)") (class "Default")
      (node (ref "C16") (pin "2") (pinfunction "2_2") (pintype "passive"))
      (node (ref "IC5") (pin "9") (pinfunction "-IN_9") (pintype "input"))
      (node (ref "R13") (pin "P$2") (pinfunction "2_P$2") (pintype "passive"))
    )
    (net (code "50") (name "Net-(IC5C-OUT)") (class "Default")
      (node (ref "C11") (pin "1") (pinfunction "1_1") (pintype "passive"))
      (node (ref "C14") (pin "2") (pinfunction "2_2") (pintype "passive"))
      (node (ref "IC5") (pin "8") (pinfunction "OUT_8") (pintype "output"))
      (node (ref "R13") (pin "P$1") (pinfunction "1_P$1") (pintype "passive"))
    )
    (net (code "51") (name "Net-(IC6A--IN)") (class "Default")
      (node (ref "IC6") (pin "2") (pinfunction "-IN_2") (pintype "input"))
      (node (ref "POT4") (pin "1") (pinfunction "CCW_1") (pintype "passive"))
      (node (ref "POT4") (pin "2") (pinfunction "WIPER_2") (pintype "passive"))
      (node (ref "R17") (pin "P$1") (pinfunction "1_P$1") (pintype "passive"))
      (node (ref "R18") (pin "P$1") (pinfunction "1_P$1") (pintype "passive"))
    )
    (net (code "52") (name "Net-(IC6A-OUT)") (class "Default")
      (node (ref "IC6") (pin "1") (pinfunction "OUT_1") (pintype "output"))
      (node (ref "POT4") (pin "3") (pinfunction "CW_3") (pintype "passive"))
      (node (ref "R20") (pin "P$2") (pinfunction "2_P$2") (pintype "passive"))
      (node (ref "R23") (pin "P$2") (pinfunction "2_P$2") (pintype "passive"))
      (node (ref "R25") (pin "P$2") (pinfunction "2_P$2") (pintype "passive"))
    )
    (net (code "53") (name "Net-(IC7-+IN)") (class "Default")
      (node (ref "IC7") (pin "3") (pinfunction "+IN_3") (pintype "input"))
      (node (ref "POT5") (pin "2") (pinfunction "WIPER_2") (pintype "passive"))
    )
    (net (code "54") (name "Net-(IC7-OUT)") (class "Default")
      (node (ref "C20") (pin "1") (pinfunction "1_1") (pintype "passive"))
      (node (ref "C21") (pin "1") (pinfunction "1_1") (pintype "passive"))
      (node (ref "IC7") (pin "5") (pinfunction "OUT_5") (pintype "output"))
    )
    (net (code "55") (name "Net-(IC8C--IN)") (class "Default")
      (node (ref "C25") (pin "2") (pinfunction "2_2") (pintype "passive"))
      (node (ref "C26") (pin "2") (pinfunction "2_2") (pintype "passive"))
      (node (ref "C27") (pin "2") (pinfunction "2_2") (pintype "passive"))
      (node (ref "IC8") (pin "9") (pinfunction "-IN_9") (pintype "input"))
      (node (ref "R22") (pin "P$1") (pinfunction "1_P$1") (pintype "passive"))
    )
    (net (code "56") (name "Net-(IC8C-OUT)") (class "Default")
      (node (ref "C18") (pin "1") (pinfunction "1_1") (pintype "passive"))
      (node (ref "IC8") (pin "8") (pinfunction "OUT_8") (pintype "output"))
      (node (ref "IC9") (pin "12") (pinfunction "+IN_12") (pintype "input"))
      (node (ref "R21") (pin "P$1") (pinfunction "1_P$1") (pintype "passive"))
      (node (ref "R24") (pin "P$1") (pinfunction "1_P$1") (pintype "passive"))
      (node (ref "R26") (pin "P$1") (pinfunction "1_P$1") (pintype "passive"))
    )
    (net (code "57") (name "Net-(IC9D--IN)") (class "Default")
      (node (ref "IC9") (pin "13") (pinfunction "-IN_13") (pintype "input"))
      (node (ref "R28") (pin "P$1") (pinfunction "1_P$1") (pintype "passive"))
      (node (ref "R29") (pin "P$2") (pinfunction "2_P$2") (pintype "passive"))
    )
    (net (code "58") (name "Net-(IC9D-OUT)") (class "Default")
      (node (ref "C19") (pin "1") (pinfunction "1_1") (pintype "passive"))
      (node (ref "C5") (pin "1") (pinfunction "1_1") (pintype "passive"))
      (node (ref "IC9") (pin "14") (pinfunction "OUT_14") (pintype "output"))
      (node (ref "R10") (pin "P$2") (pinfunction "2_P$2") (pintype "passive"))
      (node (ref "R29") (pin "P$1") (pinfunction "1_P$1") (pintype "passive"))
    )
    (net (code "59") (name "Net-(POT1-CCW)") (class "Default")
      (node (ref "C7") (pin "2") (pinfunction "2_2") (pintype "passive"))
      (node (ref "POT1") (pin "1") (pinfunction "CCW_1") (pintype "passive"))
    )
    (net (code "60") (name "Net-(POT2-CCW)") (class "Default")
      (node (ref "C8") (pin "2") (pinfunction "2_2") (pintype "passive"))
      (node (ref "POT2") (pin "1") (pinfunction "CCW_1") (pintype "passive"))
    )
    (net (code "61") (name "Net-(POT3-CCW)") (class "Default")
      (node (ref "C11") (pin "2") (pinfunction "2_2") (pintype "passive"))
      (node (ref "POT3") (pin "1") (pinfunction "CCW_1") (pintype "passive"))
    )
    (net (code "62") (name "Net-(POT5-CCW)") (class "Default")
      (node (ref "C18") (pin "2") (pinfunction "2_2") (pintype "passive"))
      (node (ref "POT5") (pin "1") (pinfunction "CCW_1") (pintype "passive"))
    )
    (net (code "63") (name "Net-(POT6-CCW)") (class "Default")
      (node (ref "C23") (pin "1") (pinfunction "1_1") (pintype "passive"))
      (node (ref "POT6") (pin "1") (pinfunction "CCW_1") (pintype "passive"))
      (node (ref "R20") (pin "P$1") (pinfunction "1_P$1") (pintype "passive"))
    )
    (net (code "64") (name "Net-(POT6-CW)") (class "Default")
      (node (ref "C23") (pin "2") (pinfunction "2_2") (pintype "passive"))
      (node (ref "POT6") (pin "3") (pinfunction "CW_3") (pintype "passive"))
      (node (ref "R21") (pin "P$2") (pinfunction "2_P$2") (pintype "passive"))
    )
    (net (code "65") (name "Net-(POT6-WIPER)") (class "Default")
      (node (ref "POT6") (pin "2") (pinfunction "WIPER_2") (pintype "passive"))
      (node (ref "R22") (pin "P$2") (pinfunction "2_P$2") (pintype "passive"))
    )
    (net (code "66") (name "Net-(POT7-CCW)") (class "Default")
      (node (ref "C24") (pin "1") (pinfunction "1_1") (pintype "passive"))
      (node (ref "POT7") (pin "1") (pinfunction "CCW_1") (pintype "passive"))
      (node (ref "R23") (pin "P$1") (pinfunction "1_P$1") (pintype "passive"))
    )
    (net (code "67") (name "Net-(POT7-CW)") (class "Default")
      (node (ref "C24") (pin "2") (pinfunction "2_2") (pintype "passive"))
      (node (ref "POT7") (pin "3") (pinfunction "CW_3") (pintype "passive"))
      (node (ref "R24") (pin "P$2") (pinfunction "2_P$2") (pintype "passive"))
    )
    (net (code "68") (name "Net-(POT7-WIPER)") (class "Default")
      (node (ref "C25") (pin "1") (pinfunction "1_1") (pintype "passive"))
      (node (ref "POT7") (pin "2") (pinfunction "WIPER_2") (pintype "passive"))
    )
    (net (code "69") (name "Net-(POT8-CCW)") (class "Default")
      (node (ref "C28") (pin "1") (pinfunction "1_1") (pintype "passive"))
      (node (ref "POT8") (pin "1") (pinfunction "CCW_1") (pintype "passive"))
      (node (ref "R25") (pin "P$1") (pinfunction "1_P$1") (pintype "passive"))
    )
    (net (code "70") (name "Net-(POT8-CW)") (class "Default")
      (node (ref "C28") (pin "2") (pinfunction "2_2") (pintype "passive"))
      (node (ref "POT8") (pin "3") (pinfunction "CW_3") (pintype "passive"))
      (node (ref "R26") (pin "P$2") (pinfunction "2_P$2") (pintype "passive"))
    )
    (net (code "71") (name "Net-(POT8-WIPER)") (class "Default")
      (node (ref "C26") (pin "1") (pinfunction "1_1") (pintype "passive"))
      (node (ref "POT8") (pin "2") (pinfunction "WIPER_2") (pintype "passive"))
    )
    (net (code "72") (name "Net-(R7-2)") (class "Default")
      (node (ref "C6") (pin "2") (pinfunction "2_2") (pintype "passive"))
      (node (ref "R7") (pin "P$2") (pinfunction "2_P$2") (pintype "passive"))
      (node (ref "R8") (pin "P$2") (pinfunction "2_P$2") (pintype "passive"))
      (node (ref "R9") (pin "P$1") (pinfunction "1_P$1") (pintype "passive"))
    )
    (net (code "73") (name "Net-(R9-2)") (class "Default")
      (node (ref "C5") (pin "2") (pinfunction "2_2") (pintype "passive"))
      (node (ref "R9") (pin "P$2") (pinfunction "2_P$2") (pintype "passive"))
    )
    (net (code "74") (name "Net-(R10-1)") (class "Default")
      (node (ref "C10") (pin "1") (pinfunction "1_1") (pintype "passive"))
      (node (ref "C9") (pin "1") (pinfunction "1_1") (pintype "passive"))
      (node (ref "R10") (pin "P$1") (pinfunction "1_P$1") (pintype "passive"))
      (node (ref "R11") (pin "P$1") (pinfunction "1_P$1") (pintype "passive"))
    )
    (net (code "75") (name "Net-(R14-1)") (class "Default")
      (node (ref "C14") (pin "1") (pinfunction "1_1") (pintype "passive"))
      (node (ref "C16") (pin "1") (pinfunction "1_1") (pintype "passive"))
      (node (ref "C19") (pin "2") (pinfunction "2_2") (pintype "passive"))
      (node (ref "R14") (pin "P$1") (pinfunction "1_P$1") (pintype "passive"))
    )
    (net (code "76") (name "Net-(R17-2)") (class "Default")
      (node (ref "C15") (pin "2") (pinfunction "2_2") (pintype "passive"))
      (node (ref "R17") (pin "P$2") (pinfunction "2_P$2") (pintype "passive"))
    )
    (net (code "77") (name "Net-(R18-2)") (class "Default")
      (node (ref "C17") (pin "2") (pinfunction "2_2") (pintype "passive"))
      (node (ref "R18") (pin "P$2") (pinfunction "2_P$2") (pintype "passive"))
    )
    (net (code "78") (name "Net-(R19-1)") (class "Default")
      (node (ref "C20") (pin "2") (pinfunction "2_2") (pintype "passive"))
      (node (ref "R19") (pin "P$1") (pinfunction "1_P$1") (pintype "passive"))
    )
    (net (code "79") (name "Net-(R27-1)") (class "Default")
      (node (ref "C27") (pin "1") (pinfunction "1_1") (pintype "passive"))
      (node (ref "R27") (pin "P$1") (pinfunction "1_P$1") (pintype "passive"))
    )
    (net (code "80") (name "Net-(SP1-1)") (class "Default")
      (node (ref "C21") (pin "2") (pinfunction "2_2") (pintype "passive"))
      (node (ref "SP1") (pin "+") (pinfunction "1_+") (pintype "passive"))
    )
    (net (code "81") (name "VCC") (class "Default")
      (node (ref "C1") (pin "2") (pinfunction "2_2") (pintype "passive"))
      (node (ref "C12") (pin "1") (pinfunction "1_1") (pintype "passive"))
      (node (ref "C2") (pin "2") (pinfunction "2_2") (pintype "passive"))
      (node (ref "C22") (pin "1") (pinfunction "1_1") (pintype "passive"))
      (node (ref "C3") (pin "2") (pinfunction "2_2") (pintype "passive"))
      (node (ref "IC1") (pin "3") (pinfunction "P$3_3") (pintype "bidirectional"))
      (node (ref "IC1") (pin "9") (pinfunction "P$9_9") (pintype "bidirectional"))
      (node (ref "IC3") (pin "3") (pinfunction "P$3_3") (pintype "bidirectional"))
      (node (ref "IC3") (pin "9") (pinfunction "P$9_9") (pintype "bidirectional"))
      (node (ref "IC4") (pin "3") (pinfunction "P$3_3") (pintype "bidirectional"))
      (node (ref "IC4") (pin "9") (pinfunction "P$9_9") (pintype "bidirectional"))
      (node (ref "IC7") (pin "6") (pinfunction "VS_6") (pintype "power_in"))
      (node (ref "R15") (pin "P$2") (pinfunction "2_P$2") (pintype "passive"))
      (node (ref "STACK1") (pin "P$1") (pinfunction "P$1_P$1") (pintype "bidirectional"))
      (node (ref "STACK1") (pin "P$10") (pinfunction "P$10_P$10") (pintype "bidirectional"))
      (node (ref "STACK1") (pin "P$2") (pinfunction "P$2_P$2") (pintype "bidirectional"))
      (node (ref "STACK1") (pin "P$3") (pinfunction "P$3_P$3") (pintype "bidirectional"))
      (node (ref "STACK1") (pin "P$4") (pinfunction "P$4_P$4") (pintype "bidirectional"))
      (node (ref "STACK1") (pin "P$5") (pinfunction "P$5_P$5") (pintype "bidirectional"))
      (node (ref "STACK1") (pin "P$6") (pinfunction "P$6_P$6") (pintype "bidirectional"))
      (node (ref "STACK1") (pin "P$7") (pinfunction "P$7_P$7") (pintype "bidirectional"))
      (node (ref "STACK1") (pin "P$8") (pinfunction "P$8_P$8") (pintype "bidirectional"))
      (node (ref "STACK1") (pin "P$9") (pinfunction "P$9_P$9") (pintype "bidirectional"))
      (node (ref "STACK2") (pin "P$1") (pinfunction "P$1_P$1") (pintype "bidirectional"))
      (node (ref "STACK2") (pin "P$10") (pinfunction "P$10_P$10") (pintype "bidirectional"))
      (node (ref "STACK2") (pin "P$2") (pinfunction "P$2_P$2") (pintype "bidirectional"))
      (node (ref "STACK2") (pin "P$3") (pinfunction "P$3_P$3") (pintype "bidirectional"))
      (node (ref "STACK2") (pin "P$4") (pinfunction "P$4_P$4") (pintype "bidirectional"))
      (node (ref "STACK2") (pin "P$5") (pinfunction "P$5_P$5") (pintype "bidirectional"))
      (node (ref "STACK2") (pin "P$6") (pinfunction "P$6_P$6") (pintype "bidirectional"))
      (node (ref "STACK2") (pin "P$7") (pinfunction "P$7_P$7") (pintype "bidirectional"))
      (node (ref "STACK2") (pin "P$8") (pinfunction "P$8_P$8") (pintype "bidirectional"))
      (node (ref "STACK2") (pin "P$9") (pinfunction "P$9_P$9") (pintype "bidirectional"))
      (node (ref "STACK3") (pin "P$1") (pinfunction "P$1_P$1") (pintype "bidirectional"))
      (node (ref "STACK3") (pin "P$10") (pinfunction "P$10_P$10") (pintype "bidirectional"))
      (node (ref "STACK3") (pin "P$2") (pinfunction "P$2_P$2") (pintype "bidirectional"))
      (node (ref "STACK3") (pin "P$3") (pinfunction "P$3_P$3") (pintype "bidirectional"))
      (node (ref "STACK3") (pin "P$4") (pinfunction "P$4_P$4") (pintype "bidirectional"))
      (node (ref "STACK3") (pin "P$5") (pinfunction "P$5_P$5") (pintype "bidirectional"))
      (node (ref "STACK3") (pin "P$6") (pinfunction "P$6_P$6") (pintype "bidirectional"))
      (node (ref "STACK3") (pin "P$7") (pinfunction "P$7_P$7") (pintype "bidirectional"))
      (node (ref "STACK3") (pin "P$8") (pinfunction "P$8_P$8") (pintype "bidirectional"))
      (node (ref "STACK3") (pin "P$9") (pinfunction "P$9_P$9") (pintype "bidirectional"))
      (node (ref "STACK4") (pin "P$1") (pinfunction "P$1_P$1") (pintype "bidirectional"))
      (node (ref "STACK4") (pin "P$10") (pinfunction "P$10_P$10") (pintype "bidirectional"))
      (node (ref "STACK4") (pin "P$2") (pinfunction "P$2_P$2") (pintype "bidirectional"))
      (node (ref "STACK4") (pin "P$3") (pinfunction "P$3_P$3") (pintype "bidirectional"))
      (node (ref "STACK4") (pin "P$4") (pinfunction "P$4_P$4") (pintype "bidirectional"))
      (node (ref "STACK4") (pin "P$5") (pinfunction "P$5_P$5") (pintype "bidirectional"))
      (node (ref "STACK4") (pin "P$6") (pinfunction "P$6_P$6") (pintype "bidirectional"))
      (node (ref "STACK4") (pin "P$7") (pinfunction "P$7_P$7") (pintype "bidirectional"))
      (node (ref "STACK4") (pin "P$8") (pinfunction "P$8_P$8") (pintype "bidirectional"))
      (node (ref "STACK4") (pin "P$9") (pinfunction "P$9_P$9") (pintype "bidirectional"))
    )
    (net (code "82") (name "unconnected-(IC7-BYPASS-Pad7)") (class "Default")
      (node (ref "IC7") (pin "7") (pinfunction "BYPASS_7") (pintype "passive"))
    )
    (net (code "83") (name "unconnected-(IC7-GAIN-Pad1)") (class "Default")
      (node (ref "IC7") (pin "1") (pinfunction "GAIN_1") (pintype "passive"))
    )
    (net (code "84") (name "unconnected-(IC7-GAIN-Pad8)") (class "Default")
      (node (ref "IC7") (pin "8") (pinfunction "GAIN_8") (pintype "passive"))
    )
    (net (code "85") (name "unconnected-(X1-Pad2)") (class "Default")
      (node (ref "X1") (pin "2") (pinfunction "2_2") (pintype "passive"))
    )
    (net (code "86") (name "unconnected-(X1-Pad3)") (class "Default")
      (node (ref "X1") (pin "3") (pinfunction "3_3") (pintype "passive"))
    )
  )
)
